# accel-chain.net
KiCad netlist of a schematic drawn in EAGLE
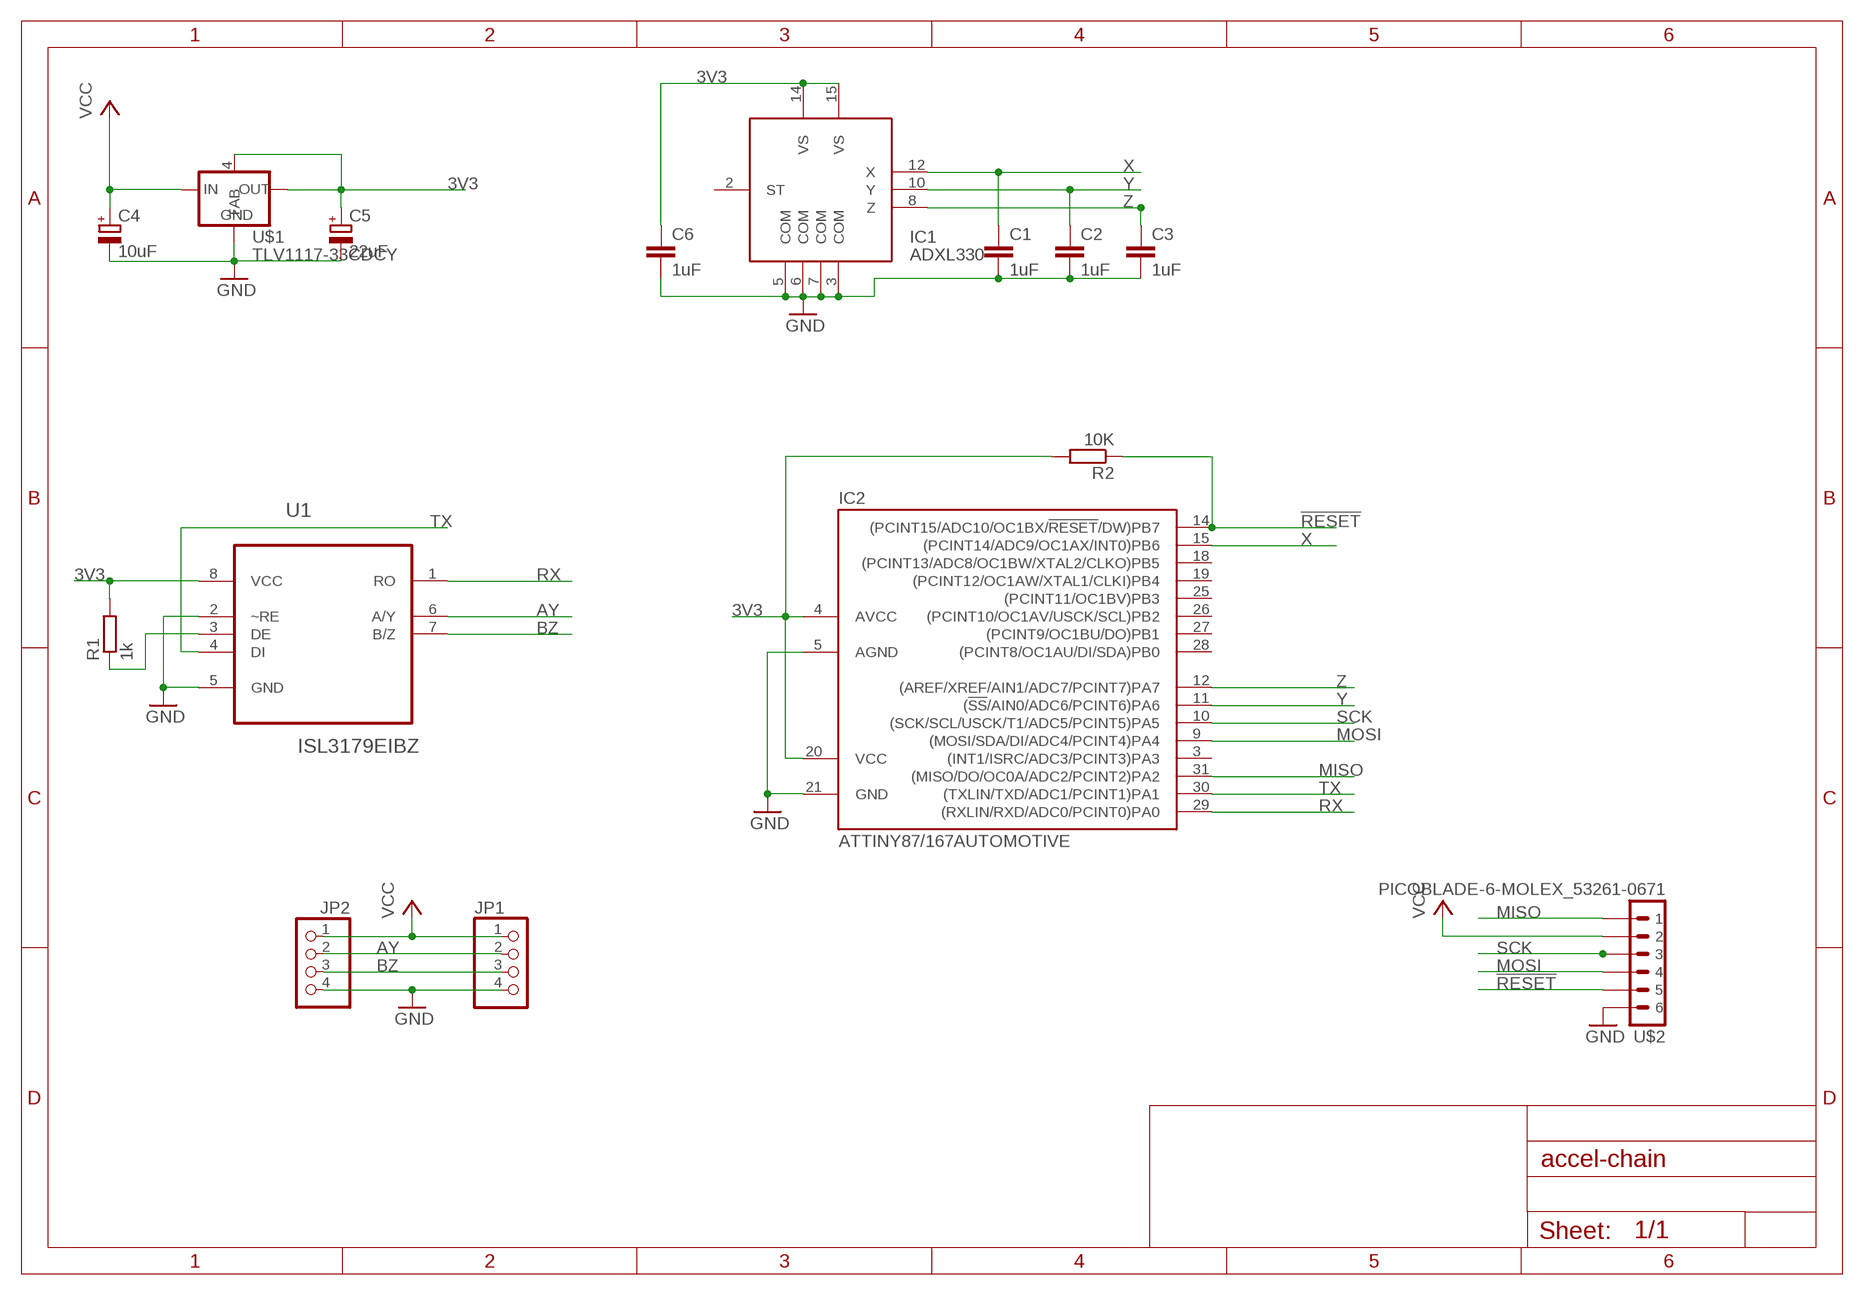
[diagram p0: schematic, sheet 1]

(export (version "E")
  (design (tool "Eeschema 10.0.6"))
  (components
    (comp (ref "C1")
      (value "1uF")
      (footprint "eagle-import:C0805")
      (libsource (lib "eagle-import") (part "C-EUC0805"))
    )
    (comp (ref "C2")
      (value "1uF")
      (footprint "eagle-import:C0805")
      (libsource (lib "eagle-import") (part "C-EUC0805"))
    )
    (comp (ref "C3")
      (value "1uF")
      (footprint "eagle-import:C0805")
      (libsource (lib "eagle-import") (part "C-EUC0805"))
    )
    (comp (ref "C4")
      (value "10uF")
      (footprint "eagle-import:A_3216-18R")
      (libsource (lib "eagle-import") (part "CPOL-EUA/3216-18R"))
    )
    (comp (ref "C5")
      (value "22uF")
      (footprint "eagle-import:A_3216-18R")
      (libsource (lib "eagle-import") (part "CPOL-EUA/3216-18R"))
    )
    (comp (ref "C6")
      (value "1uF")
      (footprint "eagle-import:C0805")
      (libsource (lib "eagle-import") (part "C-EUC0805"))
    )
    (comp (ref "IC1")
      (value "ADXL330")
      (footprint "eagle-import:LFCSP16")
      (libsource (lib "eagle-import") (part "ADXL330"))
    )
    (comp (ref "IC2")
      (value "ATTINY87/167AUTOMOTIVE")
      (footprint "eagle-import:MLF32")
      (libsource (lib "eagle-import") (part "ATTINY87/167AUTOMOTIVE"))
    )
    (comp (ref "JP1")
      (value "PINHD-1X4")
      (footprint "eagle-import:1X04")
      (libsource (lib "eagle-import") (part "PINHD-1X4"))
    )
    (comp (ref "JP2")
      (value "PINHD-1X4")
      (footprint "eagle-import:1X04")
      (libsource (lib "eagle-import") (part "PINHD-1X4"))
    )
    (comp (ref "R1")
      (value "1k")
      (footprint "eagle-import:R0805")
      (libsource (lib "eagle-import") (part "R-EU_R0805"))
    )
    (comp (ref "R2")
      (value "10K")
      (footprint "eagle-import:R0805")
      (libsource (lib "eagle-import") (part "R-EU_R0805"))
    )
    (comp (ref "U$1")
      (value "TLV1117-33CDCY")
      (footprint "eagle-import:SOT223")
      (libsource (lib "eagle-import") (part "TLV1117-33CDCY"))
    )
    (comp (ref "U$2")
      (value "PICOBLADE-6-MOLEX_53261-0671")
      (footprint "eagle-import:PICOBLADE_6-MOLEX_53261-0671")
      (fields (field (name "MANUFACTURER") "Molex") (field (name "MPN") "53261-0671"))
      (libsource (lib "eagle-import") (part "PICOBLADE-6-MOLEX_53261-0671"))
    )
    (comp (ref "U1")
      (value "ISL3179EIBZ")
      (footprint "eagle-import:SOIC127P600X175-8N")
      (libsource (lib "eagle-import") (part "ISL3179EIBZ"))
    )
  )
  (nets
    (net (code "1") (name "/3V3") (class "Default")
      (node (ref "C5") (pin "+") (pinfunction "+_+") (pintype "passive"))
      (node (ref "C6") (pin "1") (pinfunction "1_1") (pintype "passive"))
      (node (ref "IC1") (pin "14") (pinfunction "VS_14") (pintype "power_in"))
      (node (ref "IC1") (pin "15") (pinfunction "VS_15") (pintype "power_in"))
      (node (ref "IC2") (pin "20") (pinfunction "VCC_20") (pintype "power_in"))
      (node (ref "IC2") (pin "4") (pinfunction "AVCC_4") (pintype "bidirectional"))
      (node (ref "R1") (pin "2") (pinfunction "2_2") (pintype "passive"))
      (node (ref "R2") (pin "2") (pinfunction "2_2") (pintype "passive"))
      (node (ref "U$1") (pin "2") (pinfunction "OUT_2") (pintype "passive"))
      (node (ref "U$1") (pin "4") (pinfunction "TAB_4") (pintype "passive"))
      (node (ref "U1") (pin "8") (pinfunction "VCC_8") (pintype "power_in"))
    )
    (net (code "2") (name "/AY") (class "Default")
      (node (ref "JP1") (pin "2") (pinfunction "2_2") (pintype "passive"))
      (node (ref "JP2") (pin "2") (pinfunction "2_2") (pintype "passive"))
      (node (ref "U1") (pin "6") (pinfunction "A/Y_6") (pintype "bidirectional"))
    )
    (net (code "3") (name "/BZ") (class "Default")
      (node (ref "JP1") (pin "3") (pinfunction "3_3") (pintype "passive"))
      (node (ref "JP2") (pin "3") (pinfunction "3_3") (pintype "passive"))
      (node (ref "U1") (pin "7") (pinfunction "B/Z_7") (pintype "bidirectional"))
    )
    (net (code "4") (name "/MISO") (class "Default")
      (node (ref "IC2") (pin "31") (pinfunction "(MISO/DO/OC0A/ADC2/PCINT2)PA2_31") (pintype "bidirectional"))
      (node (ref "U$2") (pin "1") (pinfunction "1_1") (pintype "passive"))
    )
    (net (code "5") (name "/MOSI") (class "Default")
      (node (ref "IC2") (pin "9") (pinfunction "(MOSI/SDA/DI/ADC4/PCINT4)PA4_9") (pintype "bidirectional"))
      (node (ref "U$2") (pin "4") (pinfunction "4_4") (pintype "passive"))
    )
    (net (code "6") (name "/RX") (class "Default")
      (node (ref "IC2") (pin "29") (pinfunction "(RXLIN/RXD/ADC0/PCINT0)PA0_29") (pintype "bidirectional"))
      (node (ref "U1") (pin "1") (pinfunction "RO_1") (pintype "output"))
    )
    (net (code "7") (name "/SCK") (class "Default")
      (node (ref "IC2") (pin "10") (pinfunction "(SCK/SCL/USCK/T1/ADC5/PCINT5)PA5_10") (pintype "bidirectional"))
      (node (ref "U$2") (pin "3") (pinfunction "3_3") (pintype "passive"))
    )
    (net (code "8") (name "/TX") (class "Default")
      (node (ref "IC2") (pin "30") (pinfunction "(TXLIN/TXD/ADC1/PCINT1)PA1_30") (pintype "bidirectional"))
      (node (ref "U1") (pin "4") (pinfunction "DI_4") (pintype "input"))
    )
    (net (code "9") (name "/X") (class "Default")
      (node (ref "C1") (pin "1") (pinfunction "1_1") (pintype "passive"))
      (node (ref "IC1") (pin "12") (pinfunction "X_12") (pintype "output"))
      (node (ref "IC2") (pin "15") (pinfunction "(PCINT14/ADC9/OC1AX/INT0)PB6_15") (pintype "bidirectional"))
    )
    (net (code "10") (name "/Y") (class "Default")
      (node (ref "C2") (pin "1") (pinfunction "1_1") (pintype "passive"))
      (node (ref "IC1") (pin "10") (pinfunction "Y_10") (pintype "output"))
      (node (ref "IC2") (pin "11") (pinfunction "(~{SS}/AIN0/ADC6/PCINT6)PA6_11") (pintype "bidirectional"))
    )
    (net (code "11") (name "/Z") (class "Default")
      (node (ref "C3") (pin "1") (pinfunction "1_1") (pintype "passive"))
      (node (ref "IC1") (pin "8") (pinfunction "Z_8") (pintype "output"))
      (node (ref "IC2") (pin "12") (pinfunction "(AREF/XREF/AIN1/ADC7/PCINT7)PA7_12") (pintype "bidirectional"))
    )
    (net (code "12") (name "/~{RESET}") (class "Default")
      (node (ref "IC2") (pin "14") (pinfunction "(PCINT15/ADC10/OC1BX/~{RESET}/DW)PB7_14") (pintype "bidirectional"))
      (node (ref "R2") (pin "1") (pinfunction "1_1") (pintype "passive"))
      (node (ref "U$2") (pin "5") (pinfunction "5_5") (pintype "passive"))
    )
    (net (code "13") (name "GND") (class "Default")
      (node (ref "C1") (pin "2") (pinfunction "2_2") (pintype "passive"))
      (node (ref "C2") (pin "2") (pinfunction "2_2") (pintype "passive"))
      (node (ref "C3") (pin "2") (pinfunction "2_2") (pintype "passive"))
      (node (ref "C4") (pin "-") (pinfunction "-_-") (pintype "passive"))
      (node (ref "C5") (pin "-") (pinfunction "-_-") (pintype "passive"))
      (node (ref "C6") (pin "2") (pinfunction "2_2") (pintype "passive"))
      (node (ref "IC1") (pin "3") (pinfunction "COM_3") (pintype "power_in"))
      (node (ref "IC1") (pin "5") (pinfunction "COM_5") (pintype "power_in"))
      (node (ref "IC1") (pin "6") (pinfunction "COM_6") (pintype "power_in"))
      (node (ref "IC1") (pin "7") (pinfunction "COM_7") (pintype "power_in"))
      (node (ref "IC2") (pin "21") (pinfunction "GND_21") (pintype "power_in"))
      (node (ref "IC2") (pin "5") (pinfunction "AGND_5") (pintype "bidirectional"))
      (node (ref "JP1") (pin "4") (pinfunction "4_4") (pintype "passive"))
      (node (ref "JP2") (pin "4") (pinfunction "4_4") (pintype "passive"))
      (node (ref "U$1") (pin "1") (pinfunction "GND_1") (pintype "input"))
      (node (ref "U$2") (pin "6") (pinfunction "6_6") (pintype "passive"))
      (node (ref "U1") (pin "2") (pinfunction "~{RE}_2") (pintype "input"))
      (node (ref "U1") (pin "5") (pinfunction "GND_5") (pintype "passive"))
    )
    (net (code "14") (name "Net-(U1-DE)") (class "Default")
      (node (ref "R1") (pin "1") (pinfunction "1_1") (pintype "passive"))
      (node (ref "U1") (pin "3") (pinfunction "DE_3") (pintype "input"))
    )
    (net (code "15") (name "VCC") (class "Default")
      (node (ref "C4") (pin "+") (pinfunction "+_+") (pintype "passive"))
      (node (ref "JP1") (pin "1") (pinfunction "1_1") (pintype "passive"))
      (node (ref "JP2") (pin "1") (pinfunction "1_1") (pintype "passive"))
      (node (ref "U$1") (pin "3") (pinfunction "IN_3") (pintype "input"))
      (node (ref "U$2") (pin "2") (pinfunction "2_2") (pintype "passive"))
    )
    (net (code "16") (name "unconnected-(IC1-ST-Pad2)") (class "Default")
      (node (ref "IC1") (pin "2") (pinfunction "ST_2") (pintype "input"))
    )
    (net (code "17") (name "unconnected-(IC2-(INT1{slash}ISRC{slash}ADC3{slash}PCINT3)PA3-Pad3)") (class "Default")
      (node (ref "IC2") (pin "3") (pinfunction "(INT1/ISRC/ADC3/PCINT3)PA3_3") (pintype "bidirectional"))
    )
    (net (code "18") (name "unconnected-(IC2-(PCINT8{slash}OC1AU{slash}DI{slash}SDA)PB0-Pad28)") (class "Default")
      (node (ref "IC2") (pin "28") (pinfunction "(PCINT8/OC1AU/DI/SDA)PB0_28") (pintype "bidirectional"))
    )
    (net (code "19") (name "unconnected-(IC2-(PCINT9{slash}OC1BU{slash}DO)PB1-Pad27)") (class "Default")
      (node (ref "IC2") (pin "27") (pinfunction "(PCINT9/OC1BU/DO)PB1_27") (pintype "bidirectional"))
    )
    (net (code "20") (name "unconnected-(IC2-(PCINT10{slash}OC1AV{slash}USCK{slash}SCL)PB2-Pad26)") (class "Default")
      (node (ref "IC2") (pin "26") (pinfunction "(PCINT10/OC1AV/USCK/SCL)PB2_26") (pintype "bidirectional"))
    )
    (net (code "21") (name "unconnected-(IC2-(PCINT11{slash}OC1BV)PB3-Pad25)") (class "Default")
      (node (ref "IC2") (pin "25") (pinfunction "(PCINT11/OC1BV)PB3_25") (pintype "bidirectional"))
    )
    (net (code "22") (name "unconnected-(IC2-(PCINT12{slash}OC1AW{slash}XTAL1{slash}CLKI)PB4-Pad19)") (class "Default")
      (node (ref "IC2") (pin "19") (pinfunction "(PCINT12/OC1AW/XTAL1/CLKI)PB4_19") (pintype "bidirectional"))
    )
    (net (code "23") (name "unconnected-(IC2-(PCINT13{slash}ADC8{slash}OC1BW{slash}XTAL2{slash}CLKO)PB5-Pad18)") (class "Default")
      (node (ref "IC2") (pin "18") (pinfunction "(PCINT13/ADC8/OC1BW/XTAL2/CLKO)PB5_18") (pintype "bidirectional"))
    )
  )
)
